# perfScm.net
KiCad netlist of a schematic drawn in EAGLE
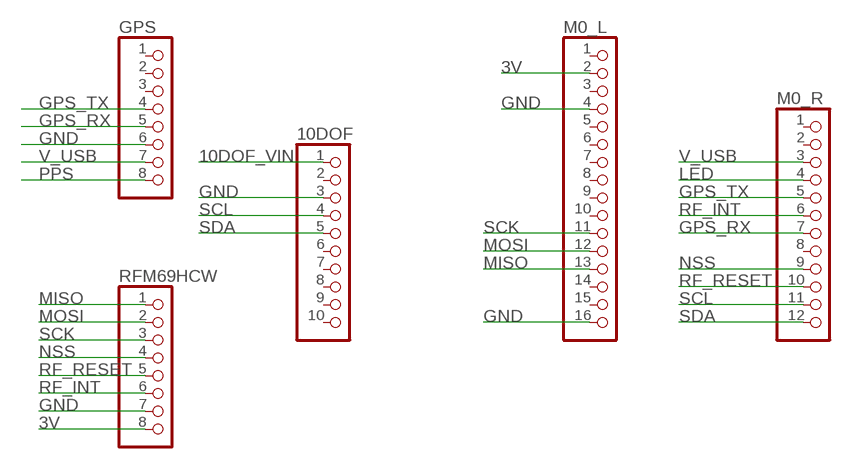
[diagram p0: schematic, sheet 1]

(export (version "E")
  (design (tool "Eeschema 10.0.6"))
  (components
    (comp (ref "10DOF")
      (value "PINHD-1X10")
      (footprint "eagle-import:1X10")
      (libsource (lib "eagle-import") (part "PINHD-1X10"))
    )
    (comp (ref "GPS")
      (value "PINHD-1X8")
      (footprint "eagle-import:1X08")
      (libsource (lib "eagle-import") (part "PINHD-1X8"))
    )
    (comp (ref "M0_L")
      (value "PINHD-1X16")
      (footprint "eagle-import:1X16")
      (libsource (lib "eagle-import") (part "PINHD-1X16"))
    )
    (comp (ref "M0_R")
      (value "PINHD-1X12")
      (footprint "eagle-import:1X12")
      (libsource (lib "eagle-import") (part "PINHD-1X12"))
    )
    (comp (ref "RFM69HCW")
      (value "PINHD-1X8")
      (footprint "eagle-import:1X08")
      (libsource (lib "eagle-import") (part "PINHD-1X8"))
    )
  )
  (nets
    (net (code "1") (name "/3V") (class "Default")
      (node (ref "M0_L") (pin "2") (pinfunction "2_2") (pintype "passive"))
      (node (ref "RFM69HCW") (pin "8") (pinfunction "8_8") (pintype "passive"))
    )
    (net (code "2") (name "/10DOF_VIN") (class "Default")
      (node (ref "10DOF") (pin "1") (pinfunction "1_1") (pintype "passive"))
    )
    (net (code "3") (name "/GND") (class "Default")
      (node (ref "10DOF") (pin "3") (pinfunction "3_3") (pintype "passive"))
      (node (ref "GPS") (pin "6") (pinfunction "6_6") (pintype "passive"))
      (node (ref "M0_L") (pin "16") (pinfunction "16_16") (pintype "passive"))
      (node (ref "M0_L") (pin "4") (pinfunction "4_4") (pintype "passive"))
      (node (ref "RFM69HCW") (pin "7") (pinfunction "7_7") (pintype "passive"))
    )
    (net (code "4") (name "/GPS_RX") (class "Default")
      (node (ref "GPS") (pin "5") (pinfunction "5_5") (pintype "passive"))
      (node (ref "M0_R") (pin "7") (pinfunction "7_7") (pintype "passive"))
    )
    (net (code "5") (name "/GPS_TX") (class "Default")
      (node (ref "GPS") (pin "4") (pinfunction "4_4") (pintype "passive"))
      (node (ref "M0_R") (pin "5") (pinfunction "5_5") (pintype "passive"))
    )
    (net (code "6") (name "/LED") (class "Default")
      (node (ref "M0_R") (pin "4") (pinfunction "4_4") (pintype "passive"))
    )
    (net (code "7") (name "/MISO") (class "Default")
      (node (ref "M0_L") (pin "13") (pinfunction "13_13") (pintype "passive"))
      (node (ref "RFM69HCW") (pin "1") (pinfunction "1_1") (pintype "passive"))
    )
    (net (code "8") (name "/MOSI") (class "Default")
      (node (ref "M0_L") (pin "12") (pinfunction "12_12") (pintype "passive"))
      (node (ref "RFM69HCW") (pin "2") (pinfunction "2_2") (pintype "passive"))
    )
    (net (code "9") (name "/NSS") (class "Default")
      (node (ref "M0_R") (pin "9") (pinfunction "9_9") (pintype "passive"))
      (node (ref "RFM69HCW") (pin "4") (pinfunction "4_4") (pintype "passive"))
    )
    (net (code "10") (name "/PPS") (class "Default")
      (node (ref "GPS") (pin "8") (pinfunction "8_8") (pintype "passive"))
    )
    (net (code "11") (name "/RF_INT") (class "Default")
      (node (ref "M0_R") (pin "6") (pinfunction "6_6") (pintype "passive"))
      (node (ref "RFM69HCW") (pin "6") (pinfunction "6_6") (pintype "passive"))
    )
    (net (code "12") (name "/RF_RESET") (class "Default")
      (node (ref "M0_R") (pin "10") (pinfunction "10_10") (pintype "passive"))
      (node (ref "RFM69HCW") (pin "5") (pinfunction "5_5") (pintype "passive"))
    )
    (net (code "13") (name "/SCK") (class "Default")
      (node (ref "M0_L") (pin "11") (pinfunction "11_11") (pintype "passive"))
      (node (ref "RFM69HCW") (pin "3") (pinfunction "3_3") (pintype "passive"))
    )
    (net (code "14") (name "/SCL") (class "Default")
      (node (ref "10DOF") (pin "4") (pinfunction "4_4") (pintype "passive"))
      (node (ref "M0_R") (pin "11") (pinfunction "11_11") (pintype "passive"))
    )
    (net (code "15") (name "/SDA") (class "Default")
      (node (ref "10DOF") (pin "5") (pinfunction "5_5") (pintype "passive"))
      (node (ref "M0_R") (pin "12") (pinfunction "12_12") (pintype "passive"))
    )
    (net (code "16") (name "/V_USB") (class "Default")
      (node (ref "GPS") (pin "7") (pinfunction "7_7") (pintype "passive"))
      (node (ref "M0_R") (pin "3") (pinfunction "3_3") (pintype "passive"))
    )
    (net (code "17") (name "unconnected-(10DOF-Pad2)") (class "Default")
      (node (ref "10DOF") (pin "2") (pinfunction "2_2") (pintype "passive"))
    )
    (net (code "18") (name "unconnected-(10DOF-Pad6)") (class "Default")
      (node (ref "10DOF") (pin "6") (pinfunction "6_6") (pintype "passive"))
    )
    (net (code "19") (name "unconnected-(10DOF-Pad7)") (class "Default")
      (node (ref "10DOF") (pin "7") (pinfunction "7_7") (pintype "passive"))
    )
    (net (code "20") (name "unconnected-(10DOF-Pad8)") (class "Default")
      (node (ref "10DOF") (pin "8") (pinfunction "8_8") (pintype "passive"))
    )
    (net (code "21") (name "unconnected-(10DOF-Pad9)") (class "Default")
      (node (ref "10DOF") (pin "9") (pinfunction "9_9") (pintype "passive"))
    )
    (net (code "22") (name "unconnected-(10DOF-Pad10)") (class "Default")
      (node (ref "10DOF") (pin "10") (pinfunction "10_10") (pintype "passive"))
    )
    (net (code "23") (name "unconnected-(GPS-Pad1)") (class "Default")
      (node (ref "GPS") (pin "1") (pinfunction "1_1") (pintype "passive"))
    )
    (net (code "24") (name "unconnected-(GPS-Pad2)") (class "Default")
      (node (ref "GPS") (pin "2") (pinfunction "2_2") (pintype "passive"))
    )
    (net (code "25") (name "unconnected-(GPS-Pad3)") (class "Default")
      (node (ref "GPS") (pin "3") (pinfunction "3_3") (pintype "passive"))
    )
    (net (code "26") (name "unconnected-(M0_L-Pad1)") (class "Default")
      (node (ref "M0_L") (pin "1") (pinfunction "1_1") (pintype "passive"))
    )
    (net (code "27") (name "unconnected-(M0_L-Pad3)") (class "Default")
      (node (ref "M0_L") (pin "3") (pinfunction "3_3") (pintype "passive"))
    )
    (net (code "28") (name "unconnected-(M0_L-Pad5)") (class "Default")
      (node (ref "M0_L") (pin "5") (pinfunction "5_5") (pintype "passive"))
    )
    (net (code "29") (name "unconnected-(M0_L-Pad6)") (class "Default")
      (node (ref "M0_L") (pin "6") (pinfunction "6_6") (pintype "passive"))
    )
    (net (code "30") (name "unconnected-(M0_L-Pad7)") (class "Default")
      (node (ref "M0_L") (pin "7") (pinfunction "7_7") (pintype "passive"))
    )
    (net (code "31") (name "unconnected-(M0_L-Pad8)") (class "Default")
      (node (ref "M0_L") (pin "8") (pinfunction "8_8") (pintype "passive"))
    )
    (net (code "32") (name "unconnected-(M0_L-Pad9)") (class "Default")
      (node (ref "M0_L") (pin "9") (pinfunction "9_9") (pintype "passive"))
    )
    (net (code "33") (name "unconnected-(M0_L-Pad10)") (class "Default")
      (node (ref "M0_L") (pin "10") (pinfunction "10_10") (pintype "passive"))
    )
    (net (code "34") (name "unconnected-(M0_L-Pad14)") (class "Default")
      (node (ref "M0_L") (pin "14") (pinfunction "14_14") (pintype "passive"))
    )
    (net (code "35") (name "unconnected-(M0_L-Pad15)") (class "Default")
      (node (ref "M0_L") (pin "15") (pinfunction "15_15") (pintype "passive"))
    )
    (net (code "36") (name "unconnected-(M0_R-Pad1)") (class "Default")
      (node (ref "M0_R") (pin "1") (pinfunction "1_1") (pintype "passive"))
    )
    (net (code "37") (name "unconnected-(M0_R-Pad2)") (class "Default")
      (node (ref "M0_R") (pin "2") (pinfunction "2_2") (pintype "passive"))
    )
    (net (code "38") (name "unconnected-(M0_R-Pad8)") (class "Default")
      (node (ref "M0_R") (pin "8") (pinfunction "8_8") (pintype "passive"))
    )
  )
)
